# accuphase_e202_rectifier-caps_on_pins.net
KiCad netlist of a schematic drawn in EAGLE
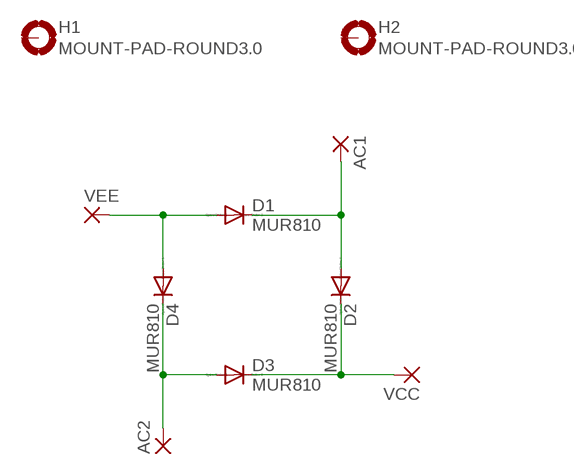
[diagram p0: schematic, sheet 1]

(export (version "E")
  (design (tool "Eeschema 10.0.6"))
  (components
    (comp (ref "AC1")
      (value "3,81/1,4")
      (footprint "eagle-import:3,81_1,4")
      (libsource (lib "eagle-import") (part "3,81/1,4"))
    )
    (comp (ref "AC2")
      (value "3,81/1,4")
      (footprint "eagle-import:3,81_1,4")
      (libsource (lib "eagle-import") (part "3,81/1,4"))
    )
    (comp (ref "D1")
      (value "MUR810")
      (footprint "eagle-import:TO220ACS")
      (libsource (lib "eagle-import") (part "MUR810"))
    )
    (comp (ref "D2")
      (value "MUR810")
      (footprint "eagle-import:TO220ACS")
      (libsource (lib "eagle-import") (part "MUR810"))
    )
    (comp (ref "D3")
      (value "MUR810")
      (footprint "eagle-import:TO220ACS")
      (libsource (lib "eagle-import") (part "MUR810"))
    )
    (comp (ref "D4")
      (value "MUR810")
      (footprint "eagle-import:TO220ACS")
      (libsource (lib "eagle-import") (part "MUR810"))
    )
    (comp (ref "H1")
      (value "MOUNT-PAD-ROUND3.0")
      (footprint "eagle-import:3,0-PAD")
      (libsource (lib "eagle-import") (part "MOUNT-PAD-ROUND3.0"))
    )
    (comp (ref "H2")
      (value "MOUNT-PAD-ROUND3.0")
      (footprint "eagle-import:3,0-PAD")
      (libsource (lib "eagle-import") (part "MOUNT-PAD-ROUND3.0"))
    )
    (comp (ref "VCC")
      (value "3,81/1,4")
      (footprint "eagle-import:3,81_1,4")
      (libsource (lib "eagle-import") (part "3,81/1,4"))
    )
    (comp (ref "VEE")
      (value "3,81/1,4")
      (footprint "eagle-import:3,81_1,4")
      (libsource (lib "eagle-import") (part "3,81/1,4"))
    )
  )
  (nets
    (net (code "1") (name "Net-(AC1-P)") (class "Default")
      (node (ref "AC1") (pin "1") (pinfunction "P_1") (pintype "passive"))
      (node (ref "D1") (pin "C") (pinfunction "C_C") (pintype "passive"))
      (node (ref "D2") (pin "A") (pinfunction "A_A") (pintype "passive"))
    )
    (net (code "2") (name "Net-(AC2-P)") (class "Default")
      (node (ref "AC2") (pin "1") (pinfunction "P_1") (pintype "passive"))
      (node (ref "D3") (pin "A") (pinfunction "A_A") (pintype "passive"))
      (node (ref "D4") (pin "C") (pinfunction "C_C") (pintype "passive"))
    )
    (net (code "3") (name "Net-(VCC-P)") (class "Default")
      (node (ref "D2") (pin "C") (pinfunction "C_C") (pintype "passive"))
      (node (ref "D3") (pin "C") (pinfunction "C_C") (pintype "passive"))
      (node (ref "VCC") (pin "1") (pinfunction "P_1") (pintype "passive"))
    )
    (net (code "4") (name "Net-(VEE-P)") (class "Default")
      (node (ref "D1") (pin "A") (pinfunction "A_A") (pintype "passive"))
      (node (ref "D4") (pin "A") (pinfunction "A_A") (pintype "passive"))
      (node (ref "VEE") (pin "1") (pinfunction "P_1") (pintype "passive"))
    )
    (net (code "5") (name "unconnected-(H1-MOUNT-PadB3,0)") (class "Default")
      (node (ref "H1") (pin "B3,0") (pinfunction "MOUNT_B3,0") (pintype "passive"))
    )
    (net (code "6") (name "unconnected-(H2-MOUNT-PadB3,0)") (class "Default")
      (node (ref "H2") (pin "B3,0") (pinfunction "MOUNT_B3,0") (pintype "passive"))
    )
  )
)
